# sensors.net
KiCad netlist of a schematic drawn in Altium Designer
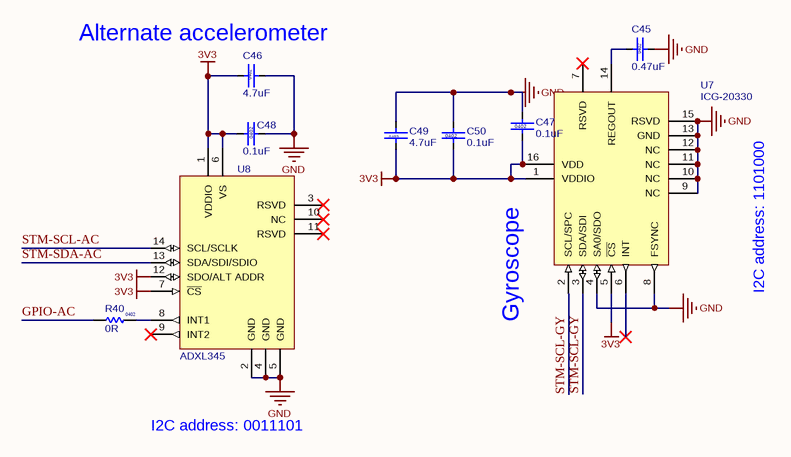
[diagram p0: sensors.SchDoc]

(export (version "E")
  (design (tool "Eeschema 10.0.6"))
  (components
    (comp (ref "C45")
      (value "0.47uF")
      (footprint "Cap 0402 HD")
      (description "Cap, Ceramic, 0.47UF 10V 10% X5R 0402")
      (fields
        (field (name "SIZE") "0402")
        (field (name "PART NUMBER") "120-00072")
        (field (name "TOLERANCE") "+/- 10%")
      )
      (libsource (lib "Arena_Parts_DB_Lib") (part "Cap Chip"))
    )
    (comp (ref "C46")
      (value "4.7uF")
      (footprint "Cap 0402 HD")
      (description "Cap, Ceramic 4.7uF 10V 20% X5R 0402")
      (fields
        (field (name "PART NUMBER") "120-00020")
        (field (name "TOLERANCE") "+/- 20%")
        (field (name "SIZE") "0402")
      )
      (libsource (lib "lib-hiony") (part "120-00020"))
    )
    (comp (ref "C47")
      (value "0.1uF")
      (footprint "Cap 0402 HD")
      (description "Cap, Ceramic 0.1uF 10V 10% X5R 0402")
      (fields
        (field (name "PART NUMBER") "120-00016")
        (field (name "MANUFACTURER") "Murata Electronics North America")
        (field (name "SIZE") "0402")
      )
      (libsource (lib "lib-hiony") (part "120-00016"))
    )
    (comp (ref "C48")
      (value "0.1uF")
      (footprint "Cap 0402 HD")
      (description "Cap, Ceramic 0.1uF 10V 10% X5R 0402")
      (fields
        (field (name "PART NUMBER") "120-00016")
        (field (name "MANUFACTURER") "Murata Electronics North America")
        (field (name "SIZE") "0402")
      )
      (libsource (lib "lib-hiony") (part "120-00016"))
    )
    (comp (ref "C49")
      (value "4.7uF")
      (footprint "Cap 0402 HD")
      (description "Cap, Ceramic 4.7uF 10V 20% X5R 0402")
      (fields
        (field (name "PART NUMBER") "120-00020")
        (field (name "TOLERANCE") "+/- 20%")
        (field (name "SIZE") "0402")
      )
      (libsource (lib "lib-hiony") (part "120-00020"))
    )
    (comp (ref "C50")
      (value "0.1uF")
      (footprint "Cap 0402 HD")
      (description "Cap, Ceramic 0.1uF 10V 10% X5R 0402")
      (fields
        (field (name "PART NUMBER") "120-00016")
        (field (name "MANUFACTURER") "Murata Electronics North America")
        (field (name "SIZE") "0402")
      )
      (libsource (lib "lib-hiony") (part "120-00016"))
    )
    (comp (ref "R40")
      (value "0R")
      (footprint "RES 0402 HD")
      (description "Resistor 0 ohm 1/16W 0402")
      (fields
        (field (name "PART NUMBER") "180-00020")
        (field (name "POWER") "1/16W")
        (field (name "SIZE") "0402")
      )
      (libsource (lib "lib-hiony") (part "180-00020"))
    )
    (comp (ref "U7")
      (value "ICG-20330")
      (footprint "ICG-20330")
      (description "SENSOR, Gyroscope, I2C, 3-AXIS, 1.7-3.45V, SMT, LGA-16, 3mmX3mm")
      (fields (field (name "MANUFACTURER PART NUMBER 1") "ICG-20330") (field (name "VOLTAGE") "1.9-3.6V"))
      (libsource (lib "ICG-20330") (part "ICG-20330"))
    )
    (comp (ref "U8")
      (value "ADXL345")
      (footprint "ADXL345")
      (description "SENSOR, ACCELEROMETER, 3-AXIS, I2C, SMT, +/-16g, LGA-14 3mmX5mm")
      (fields (field (name "MANUFACTURER PART NUMBER 1") "ADXL345"))
      (libsource (lib "ADXL345") (part "ADXL345"))
    )
  )
  (nets
    (net (code "1") (name "/GPIO-AC") (class "Default")
      (node (ref "R40") (pin "1") (pinfunction "1_1") (pintype "passive"))
    )
    (net (code "2") (name "/STM-SCL-AC") (class "Default")
      (node (ref "U8") (pin "14") (pinfunction "SCL/SCLK_14") (pintype "bidirectional"))
    )
    (net (code "3") (name "/STM-SCL-GY") (class "Default")
      (node (ref "U7") (pin "2") (pinfunction "SCL/SPC_2") (pintype "input"))
      (node (ref "U7") (pin "3") (pinfunction "SDA/SDI_3") (pintype "bidirectional"))
    )
    (net (code "4") (name "/STM-SDA-AC") (class "Default")
      (node (ref "U8") (pin "13") (pinfunction "SDA/SDI/SDIO_13") (pintype "bidirectional"))
    )
    (net (code "5") (name "3V3") (class "Default")
      (node (ref "C46") (pin "1") (pinfunction "1_1") (pintype "passive"))
      (node (ref "C47") (pin "1") (pinfunction "1_1") (pintype "passive"))
      (node (ref "C48") (pin "1") (pinfunction "1_1") (pintype "passive"))
      (node (ref "C49") (pin "1") (pinfunction "1_1") (pintype "passive"))
      (node (ref "C50") (pin "1") (pinfunction "1_1") (pintype "passive"))
      (node (ref "U7") (pin "1") (pinfunction "VDDIO_1") (pintype "power_in"))
      (node (ref "U7") (pin "16") (pinfunction "VDD_16") (pintype "power_in"))
      (node (ref "U7") (pin "5") (pinfunction "~{CS}_5") (pintype "input"))
      (node (ref "U8") (pin "1") (pinfunction "VDDIO_1") (pintype "power_in"))
      (node (ref "U8") (pin "12") (pinfunction "SDO/ALT_ADDR_12") (pintype "bidirectional"))
      (node (ref "U8") (pin "6") (pinfunction "VS_6") (pintype "power_in"))
      (node (ref "U8") (pin "7") (pinfunction "~{CS}_7") (pintype "input"))
    )
    (net (code "6") (name "GND") (class "Default")
      (node (ref "C45") (pin "2") (pinfunction "2_2") (pintype "passive"))
      (node (ref "C46") (pin "2") (pinfunction "2_2") (pintype "passive"))
      (node (ref "C47") (pin "2") (pinfunction "2_2") (pintype "passive"))
      (node (ref "C48") (pin "2") (pinfunction "2_2") (pintype "passive"))
      (node (ref "C49") (pin "2") (pinfunction "2_2") (pintype "passive"))
      (node (ref "C50") (pin "2") (pinfunction "2_2") (pintype "passive"))
      (node (ref "U7") (pin "10") (pinfunction "NC_10") (pintype "passive"))
      (node (ref "U7") (pin "11") (pinfunction "NC_11") (pintype "passive"))
      (node (ref "U7") (pin "12") (pinfunction "NC_12") (pintype "passive"))
      (node (ref "U7") (pin "13") (pinfunction "GND_13") (pintype "power_in"))
      (node (ref "U7") (pin "15") (pinfunction "RSVD_15") (pintype "passive"))
      (node (ref "U7") (pin "4") (pinfunction "SA0/SDO_4") (pintype "bidirectional"))
      (node (ref "U7") (pin "8") (pinfunction "FSYNC_8") (pintype "output"))
      (node (ref "U7") (pin "9") (pinfunction "NC_9") (pintype "passive"))
      (node (ref "U8") (pin "2") (pinfunction "GND_2") (pintype "power_in"))
      (node (ref "U8") (pin "4") (pinfunction "GND_4") (pintype "power_in"))
      (node (ref "U8") (pin "5") (pinfunction "GND_5") (pintype "power_in"))
    )
    (net (code "7") (name "Net-(U7-REGOUT)") (class "Default")
      (node (ref "C45") (pin "1") (pinfunction "1_1") (pintype "passive"))
      (node (ref "U7") (pin "14") (pinfunction "REGOUT_14") (pintype "passive"))
    )
    (net (code "8") (name "Net-(U8-INT1)") (class "Default")
      (node (ref "R40") (pin "2") (pinfunction "2_2") (pintype "passive"))
      (node (ref "U8") (pin "8") (pinfunction "INT1_8") (pintype "output"))
    )
    (net (code "9") (name "unconnected-(U7-INT-Pad6)") (class "Default")
      (node (ref "U7") (pin "6") (pinfunction "INT_6") (pintype "output+no_connect"))
    )
    (net (code "10") (name "unconnected-(U7-RSVD-Pad7)") (class "Default")
      (node (ref "U7") (pin "7") (pinfunction "RSVD_7") (pintype "passive+no_connect"))
    )
    (net (code "11") (name "unconnected-(U8-INT2-Pad9)") (class "Default")
      (node (ref "U8") (pin "9") (pinfunction "INT2_9") (pintype "output+no_connect"))
    )
    (net (code "12") (name "unconnected-(U8-NC-Pad10)") (class "Default")
      (node (ref "U8") (pin "10") (pinfunction "NC_10") (pintype "passive+no_connect"))
    )
    (net (code "13") (name "unconnected-(U8-RSVD-Pad3)") (class "Default")
      (node (ref "U8") (pin "3") (pinfunction "RSVD_3") (pintype "passive+no_connect"))
    )
    (net (code "14") (name "unconnected-(U8-RSVD-Pad11)") (class "Default")
      (node (ref "U8") (pin "11") (pinfunction "RSVD_11") (pintype "passive+no_connect"))
    )
  )
)
